# 1.net
KiCad netlist of a schematic drawn in EAGLE
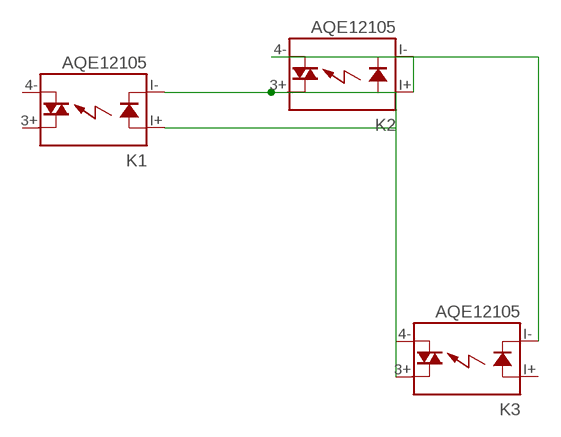
[diagram p0: schematic, sheet 1]

(export (version "E")
  (design (tool "Eeschema 10.0.6"))
  (components
    (comp (ref "K1")
      (value "AQE12105")
      (footprint "eagle-import:AQE")
      (libsource (lib "eagle-import") (part "AQE12105"))
    )
    (comp (ref "K2")
      (value "AQE12105")
      (footprint "eagle-import:AQE")
      (libsource (lib "eagle-import") (part "AQE12105"))
    )
    (comp (ref "K3")
      (value "AQE12105")
      (footprint "eagle-import:AQE")
      (libsource (lib "eagle-import") (part "AQE12105"))
    )
  )
  (nets
    (net (code "1") (name "Net-(K1-A)") (class "Default")
      (node (ref "K1") (pin "I+") (pinfunction "A_I+") (pintype "passive"))
      (node (ref "K3") (pin "4-") (pinfunction "DS2_4-") (pintype "passive"))
    )
    (net (code "2") (name "Net-(K1-K)") (class "Default")
      (node (ref "K1") (pin "I-") (pinfunction "K_I-") (pintype "passive"))
      (node (ref "K2") (pin "3+") (pinfunction "DS1_3+") (pintype "passive"))
      (node (ref "K3") (pin "3+") (pinfunction "DS1_3+") (pintype "passive"))
    )
    (net (code "3") (name "Net-(K2-A)") (class "Default")
      (node (ref "K2") (pin "I+") (pinfunction "A_I+") (pintype "passive"))
      (node (ref "K2") (pin "I-") (pinfunction "K_I-") (pintype "passive"))
    )
    (net (code "4") (name "Net-(K2-DS2)") (class "Default")
      (node (ref "K2") (pin "4-") (pinfunction "DS2_4-") (pintype "passive"))
      (node (ref "K3") (pin "I-") (pinfunction "K_I-") (pintype "passive"))
    )
    (net (code "5") (name "unconnected-(K1-DS1-Pad3+)") (class "Default")
      (node (ref "K1") (pin "3+") (pinfunction "DS1_3+") (pintype "passive"))
    )
    (net (code "6") (name "unconnected-(K1-DS2-Pad4-)") (class "Default")
      (node (ref "K1") (pin "4-") (pinfunction "DS2_4-") (pintype "passive"))
    )
    (net (code "7") (name "unconnected-(K3-A-PadI+)") (class "Default")
      (node (ref "K3") (pin "I+") (pinfunction "A_I+") (pintype "passive"))
    )
  )
)
